# reefpi_pico_power.net
KiCad netlist of a schematic drawn in Altium Designer
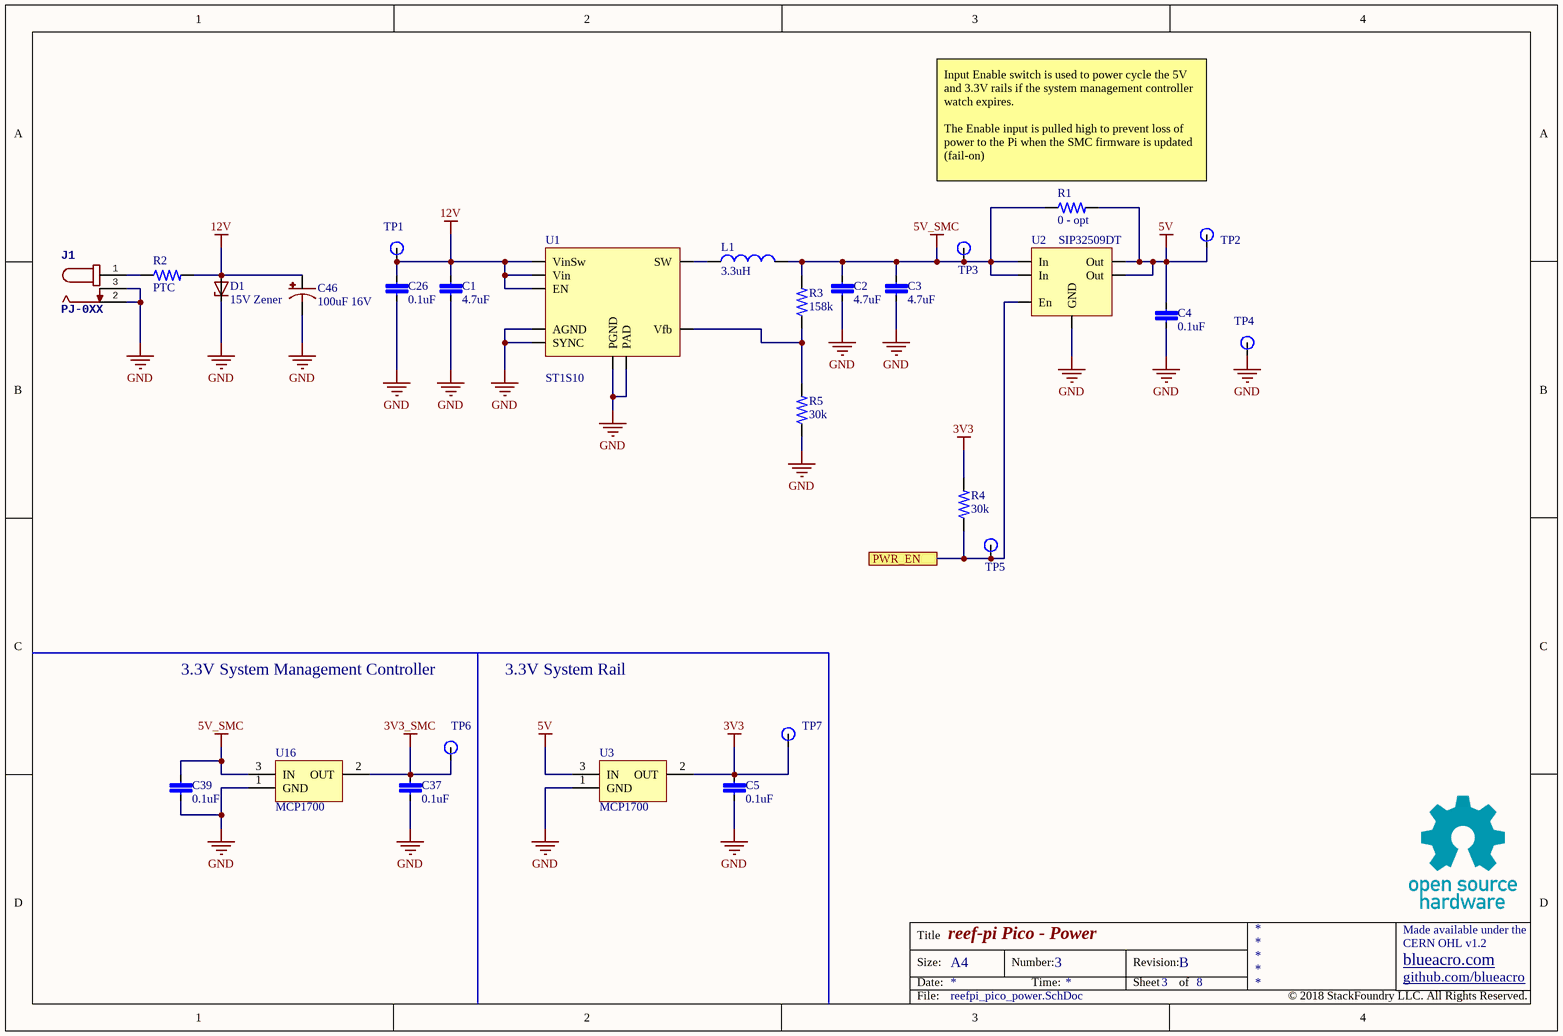
[diagram p0: reefpi_pico_power.SchDoc]

(export (version "E")
  (design (tool "Eeschema 10.0.6"))
  (components
    (comp (ref "C1") (value "4.7uF") (footprint "C1210") (libsource (lib "rcl") (part "C-EU")))
    (comp (ref "C2") (value "4.7uF") (footprint "C1210") (libsource (lib "rcl") (part "C-EU")))
    (comp (ref "C3") (value "4.7uF") (footprint "C1210") (libsource (lib "rcl") (part "C-EU")))
    (comp (ref "C4") (value "0.1uF") (footprint "C0603") (libsource (lib "rcl") (part "C-EU")))
    (comp (ref "C5") (value "0.1uF") (footprint "C0603") (libsource (lib "rcl") (part "C-EU")))
    (comp (ref "C26") (value "0.1uF") (footprint "C0603") (libsource (lib "rcl") (part "C-EU")))
    (comp (ref "C37") (value "0.1uF") (footprint "C0603") (libsource (lib "rcl") (part "C-EU")))
    (comp (ref "C39") (value "0.1uF") (footprint "C0603") (libsource (lib "rcl") (part "C-EU")))
    (comp (ref "C46") (value "100uF 16V") (footprint "PANASONIC_D") (libsource (lib "rcl") (part "CPOL-US")))
    (comp (ref "D1") (value "15V Zener") (footprint "SMA") (libsource (lib "general") (part "ZENER-DIODE")))
    (comp (ref "J1") (value "PJ-0XX") (footprint "PJ-036AH") (libsource (lib "connectors") (part "PJ-0XX")))
    (comp (ref "L1") (value "3.3uH") (footprint "ASPI_0628") (libsource (lib "rcl") (part "L-US")))
    (comp (ref "R1") (value "0 - opt") (footprint "R1206") (libsource (lib "rcl") (part "R-US")))
    (comp (ref "R2") (value "PTC") (footprint "R2920") (libsource (lib "rcl") (part "R-US")))
    (comp (ref "R3") (value "158k") (footprint "R0603") (libsource (lib "rcl") (part "R-US")))
    (comp (ref "R4") (value "30k") (footprint "R0603") (libsource (lib "rcl") (part "R-US")))
    (comp (ref "R5") (value "30k") (footprint "R0603") (libsource (lib "rcl") (part "R-US")))
    (comp (ref "TP1") (value "TP") (footprint "TP_0.89mm") (libsource (lib "testpoints") (part "TP")))
    (comp (ref "TP2") (value "TP") (footprint "TP_0.89mm") (libsource (lib "testpoints") (part "TP")))
    (comp (ref "TP3") (value "TP") (footprint "TP_0.89mm") (libsource (lib "testpoints") (part "TP")))
    (comp (ref "TP4") (value "TP") (footprint "TP_0.89mm") (libsource (lib "testpoints") (part "TP")))
    (comp (ref "TP5") (value "TP") (footprint "TP_0.89mm") (libsource (lib "testpoints") (part "TP")))
    (comp (ref "TP6") (value "TP") (footprint "TP_0.89mm") (libsource (lib "testpoints") (part "TP")))
    (comp (ref "TP7") (value "TP") (footprint "TP_0.89mm") (libsource (lib "testpoints") (part "TP")))
    (comp (ref "U1") (value "ST1S10") (footprint "VFQFPN8") (libsource (lib "stmicro") (part "ST1S10")))
    (comp (ref "U2")
      (value "SIP32509DT")
      (footprint "SOT23-6")
      (libsource (lib "general") (part "SIP32509DT"))
    )
    (comp (ref "U3") (value "MCP1700") (footprint "SOT23") (libsource (lib "microchip") (part "MCP1700")))
    (comp (ref "U16") (value "MCP1700") (footprint "SOT23") (libsource (lib "microchip") (part "MCP1700")))
  )
  (nets
    (net (code "1") (name "/PWR_EN") (class "Default")
      (node (ref "R4") (pin "1") (pinfunction "1_1") (pintype "passive"))
      (node (ref "TP5") (pin "1") (pinfunction "1_1") (pintype "passive"))
      (node (ref "U2") (pin "3") (pinfunction "En_3") (pintype "passive"))
    )
    (net (code "2") (name "3V3") (class "Default")
      (node (ref "C5") (pin "1") (pinfunction "1_1") (pintype "passive"))
      (node (ref "R4") (pin "2") (pinfunction "2_2") (pintype "passive"))
      (node (ref "TP7") (pin "1") (pinfunction "1_1") (pintype "passive"))
      (node (ref "U3") (pin "2") (pinfunction "OUT_2") (pintype "passive"))
    )
    (net (code "3") (name "3V3_SMC") (class "Default")
      (node (ref "C37") (pin "1") (pinfunction "1_1") (pintype "passive"))
      (node (ref "TP6") (pin "1") (pinfunction "1_1") (pintype "passive"))
      (node (ref "U16") (pin "2") (pinfunction "OUT_2") (pintype "passive"))
    )
    (net (code "4") (name "5V") (class "Default")
      (node (ref "C4") (pin "1") (pinfunction "1_1") (pintype "passive"))
      (node (ref "R1") (pin "2") (pinfunction "2_2") (pintype "passive"))
      (node (ref "TP2") (pin "1") (pinfunction "1_1") (pintype "passive"))
      (node (ref "U2") (pin "1") (pinfunction "Out_1") (pintype "passive"))
      (node (ref "U2") (pin "2") (pinfunction "Out_2") (pintype "passive"))
      (node (ref "U3") (pin "3") (pinfunction "IN_3") (pintype "passive"))
    )
    (net (code "5") (name "5V_SMC") (class "Default")
      (node (ref "C2") (pin "1") (pinfunction "1_1") (pintype "passive"))
      (node (ref "C3") (pin "1") (pinfunction "1_1") (pintype "passive"))
      (node (ref "C39") (pin "1") (pinfunction "1_1") (pintype "passive"))
      (node (ref "L1") (pin "2") (pinfunction "2_2") (pintype "passive"))
      (node (ref "R1") (pin "1") (pinfunction "1_1") (pintype "passive"))
      (node (ref "R3") (pin "2") (pinfunction "2_2") (pintype "passive"))
      (node (ref "TP3") (pin "1") (pinfunction "1_1") (pintype "passive"))
      (node (ref "U16") (pin "3") (pinfunction "IN_3") (pintype "passive"))
      (node (ref "U2") (pin "5") (pinfunction "In_5") (pintype "passive"))
      (node (ref "U2") (pin "6") (pinfunction "In_6") (pintype "passive"))
    )
    (net (code "6") (name "12V") (class "Default")
      (node (ref "C1") (pin "1") (pinfunction "1_1") (pintype "passive"))
      (node (ref "C26") (pin "1") (pinfunction "1_1") (pintype "passive"))
      (node (ref "C46") (pin "+") (pinfunction "+_+") (pintype "passive"))
      (node (ref "D1") (pin "A") (pinfunction "A_A") (pintype "passive"))
      (node (ref "R2") (pin "2") (pinfunction "2_2") (pintype "passive"))
      (node (ref "TP1") (pin "1") (pinfunction "1_1") (pintype "passive"))
      (node (ref "U1") (pin "1") (pinfunction "Vin_1") (pintype "passive"))
      (node (ref "U1") (pin "2") (pinfunction "EN_2") (pintype "passive"))
      (node (ref "U1") (pin "6") (pinfunction "VinSw_6") (pintype "passive"))
    )
    (net (code "7") (name "GND") (class "Default")
      (node (ref "C1") (pin "2") (pinfunction "2_2") (pintype "passive"))
      (node (ref "C2") (pin "2") (pinfunction "2_2") (pintype "passive"))
      (node (ref "C26") (pin "2") (pinfunction "2_2") (pintype "passive"))
      (node (ref "C3") (pin "2") (pinfunction "2_2") (pintype "passive"))
      (node (ref "C37") (pin "2") (pinfunction "2_2") (pintype "passive"))
      (node (ref "C39") (pin "2") (pinfunction "2_2") (pintype "passive"))
      (node (ref "C4") (pin "2") (pinfunction "2_2") (pintype "passive"))
      (node (ref "C46") (pin "-") (pinfunction "-_-") (pintype "passive"))
      (node (ref "C5") (pin "2") (pinfunction "2_2") (pintype "passive"))
      (node (ref "D1") (pin "C") (pinfunction "C_C") (pintype "passive"))
      (node (ref "J1") (pin "2") (pinfunction "2_2") (pintype "passive"))
      (node (ref "J1") (pin "3") (pinfunction "3_3") (pintype "passive"))
      (node (ref "R5") (pin "1") (pinfunction "1_1") (pintype "passive"))
      (node (ref "TP4") (pin "1") (pinfunction "1_1") (pintype "passive"))
      (node (ref "U1") (pin "4") (pinfunction "AGND_4") (pintype "passive"))
      (node (ref "U1") (pin "5") (pinfunction "SYNC_5") (pintype "passive"))
      (node (ref "U1") (pin "8") (pinfunction "PGND_8") (pintype "passive"))
      (node (ref "U1") (pin "PAD") (pinfunction "PAD_PAD") (pintype "passive"))
      (node (ref "U16") (pin "1") (pinfunction "GND_1") (pintype "passive"))
      (node (ref "U2") (pin "4") (pinfunction "GND_4") (pintype "passive"))
      (node (ref "U3") (pin "1") (pinfunction "GND_1") (pintype "passive"))
    )
    (net (code "8") (name "Net-(J1-Pad1)") (class "Default")
      (node (ref "J1") (pin "1") (pinfunction "1_1") (pintype "passive"))
      (node (ref "R2") (pin "1") (pinfunction "1_1") (pintype "passive"))
    )
    (net (code "9") (name "Net-(U1-SW)") (class "Default")
      (node (ref "L1") (pin "1") (pinfunction "1_1") (pintype "passive"))
      (node (ref "U1") (pin "7") (pinfunction "SW_7") (pintype "passive"))
    )
    (net (code "10") (name "Net-(U1-Vfb)") (class "Default")
      (node (ref "R3") (pin "1") (pinfunction "1_1") (pintype "passive"))
      (node (ref "R5") (pin "2") (pinfunction "2_2") (pintype "passive"))
      (node (ref "U1") (pin "3") (pinfunction "Vfb_3") (pintype "passive"))
    )
  )
)
